# I2C.net
KiCad netlist of a schematic drawn in Altium Designer
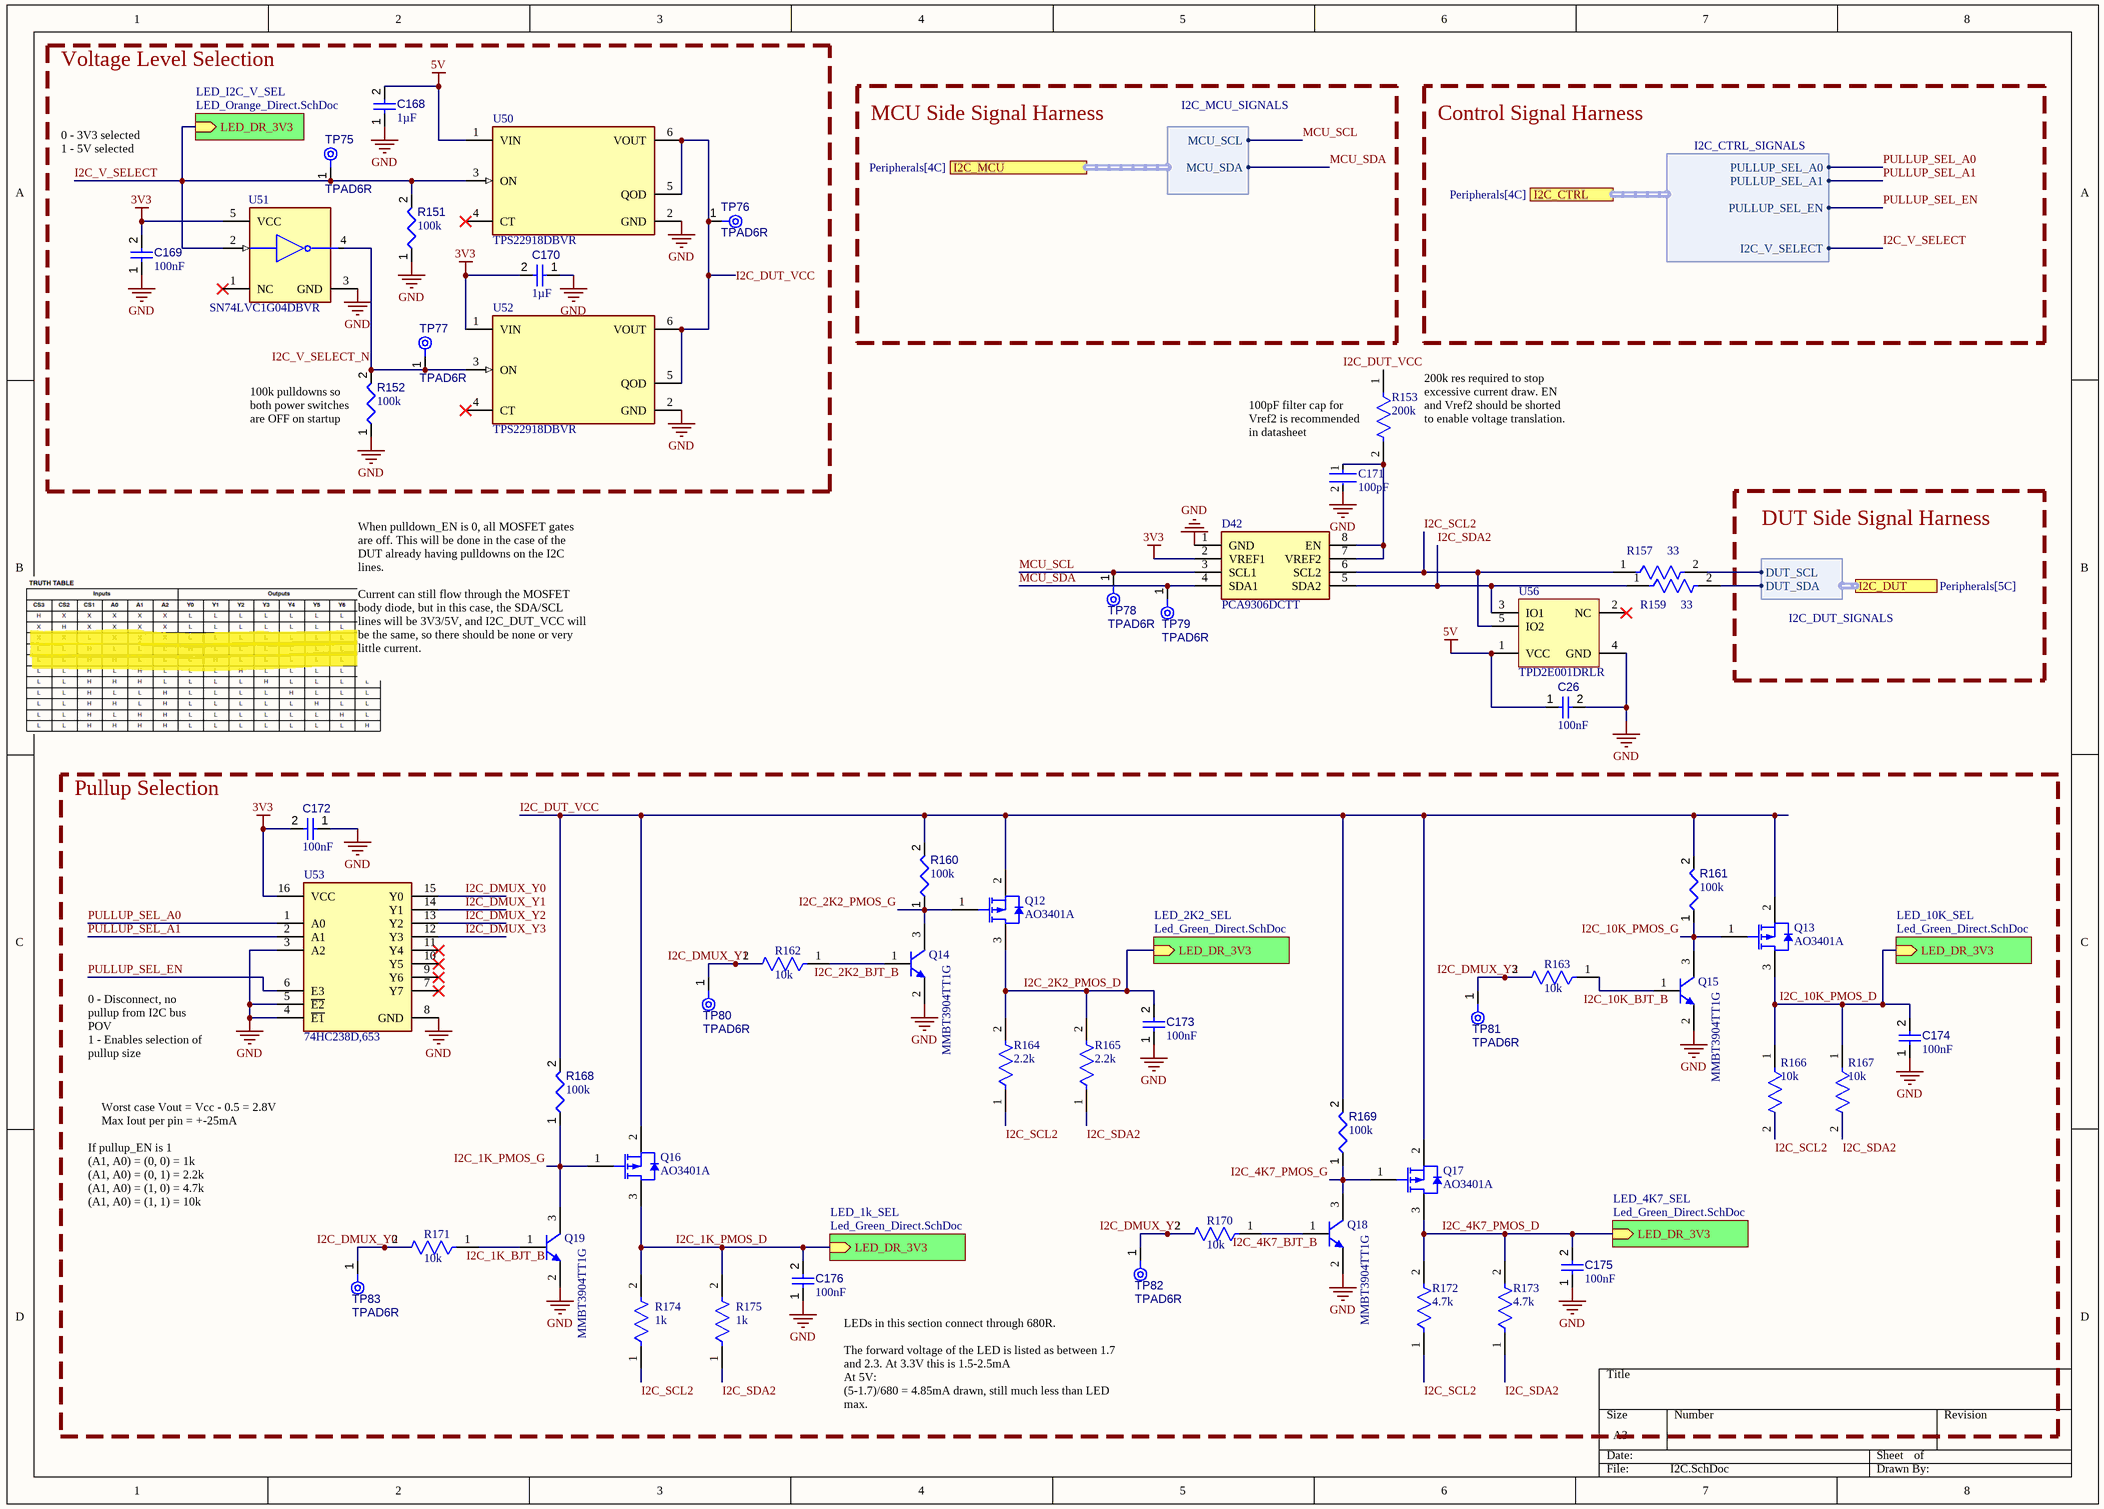
[diagram p0:  I2C.SchDoc]

(export (version "E")
  (design (tool "Eeschema 10.0.6"))
  (components
    (comp (ref "C26")
      (value "100nF")
      (footprint "CAPC1608X90X40NL10T20")
      (description "Chip Capacitor, 100 nF, +/- 10%, 50 V, 0603 (1608 Metric)")
      (fields (field (name "TOLERANCE") "10%") (field (name "Comment") "Capacitor 100 nF +/-10% 50 V 0603"))
      (libsource (lib "HIL RIG FYP") (part "CAP-NP-2"))
    )
    (comp (ref "C168")
      (value "1µF")
      (footprint "CAPC1608X90X40LL10T20")
      (description "Chip Capacitor, 1 uF, +/- 10%, 25 V, 0603 (1608 Metric)")
      (fields (field (name "TOLERANCE") "10%") (field (name "Comment") "Capacitor 1 uF +/- 10% 25 V 0603"))
      (libsource (lib "HIL RIG FYP") (part "CAP-NP-2"))
    )
    (comp (ref "C169")
      (value "100nF")
      (footprint "CAPC1608X90X40NL10T20")
      (description "Chip Capacitor, 100 nF, +/- 10%, 50 V, 0603 (1608 Metric)")
      (fields (field (name "TOLERANCE") "10%") (field (name "Comment") "Capacitor 100 nF +/-10% 50 V 0603"))
      (libsource (lib "HIL RIG FYP") (part "CAP-NP-2"))
    )
    (comp (ref "C170")
      (value "1µF")
      (footprint "CAPC1608X90X40LL10T20")
      (description "Chip Capacitor, 1 uF, +/- 10%, 25 V, 0603 (1608 Metric)")
      (fields (field (name "TOLERANCE") "10%") (field (name "Comment") "Capacitor 1 uF +/- 10% 25 V 0603"))
      (libsource (lib "HIL RIG FYP") (part "CAP-NP-2"))
    )
    (comp (ref "C171")
      (value "100pF")
      (footprint "FP-C0603C-CF-IPC_B")
      (description "50V 100pF C0G ±1% 0603 Multilayer Ceramic Capacitors MLCC - SMD/SMT ROHS")
      (fields (field (name "TOLERANCE") "1%") (field (name "Comment") "C0603C101F5GACTU"))
      (libsource (lib "HIL RIG FYP") (part "b4654b650e69147ec39a6b967a45e02"))
    )
    (comp (ref "C172")
      (value "100nF")
      (footprint "CAPC1608X90X40NL10T20")
      (description "Chip Capacitor, 100 nF, +/- 10%, 50 V, 0603 (1608 Metric)")
      (fields (field (name "TOLERANCE") "10%") (field (name "Comment") "Capacitor 100 nF +/-10% 50 V 0603"))
      (libsource (lib "HIL RIG FYP") (part "CAP-NP-2"))
    )
    (comp (ref "C173")
      (value "100nF")
      (footprint "CAPC1608X90X40NL10T20")
      (description "Chip Capacitor, 100 nF, +/- 10%, 50 V, 0603 (1608 Metric)")
      (fields (field (name "TOLERANCE") "10%") (field (name "Comment") "Capacitor 100 nF +/-10% 50 V 0603"))
      (libsource (lib "HIL RIG FYP") (part "CAP-NP-2"))
    )
    (comp (ref "C174")
      (value "100nF")
      (footprint "CAPC1608X90X40NL10T20")
      (description "Chip Capacitor, 100 nF, +/- 10%, 50 V, 0603 (1608 Metric)")
      (fields (field (name "TOLERANCE") "10%") (field (name "Comment") "Capacitor 100 nF +/-10% 50 V 0603"))
      (libsource (lib "HIL RIG FYP") (part "CAP-NP-2"))
    )
    (comp (ref "C175")
      (value "100nF")
      (footprint "CAPC1608X90X40NL10T20")
      (description "Chip Capacitor, 100 nF, +/- 10%, 50 V, 0603 (1608 Metric)")
      (fields (field (name "TOLERANCE") "10%") (field (name "Comment") "Capacitor 100 nF +/-10% 50 V 0603"))
      (libsource (lib "HIL RIG FYP") (part "CAP-NP-2"))
    )
    (comp (ref "C176")
      (value "100nF")
      (footprint "CAPC1608X90X40NL10T20")
      (description "Chip Capacitor, 100 nF, +/- 10%, 50 V, 0603 (1608 Metric)")
      (fields (field (name "TOLERANCE") "10%") (field (name "Comment") "Capacitor 100 nF +/-10% 50 V 0603"))
      (libsource (lib "HIL RIG FYP") (part "CAP-NP-2"))
    )
    (comp (ref "D42")
      (value "PCA9306DCTT")
      (footprint "SOP65P400X130-8N")
      (description "2-Bit Bidirectional I2C Bus and SMBus Voltage-Level Shifter")
      (fields (field (name "MOUSER PART NUMBER") "595-PCA9306DCTT"))
      (libsource (lib "HIL RIG FYP") (part "PCA9306DCTT"))
    )
    (comp (ref "Q12")
      (value "AO3401A")
      (footprint "AO-SOT-23-3L_V")
      (description "Transistor: P-MOSFET; unipolar; -30V; 4, 2A; 1, 4W; 85 mOhm; ; -55+150 st.C; SMD; SOT23")
      (libsource (lib "HIL RIG FYP") (part "PEMOS-GSD-3"))
    )
    (comp (ref "Q13")
      (value "AO3401A")
      (footprint "AO-SOT-23-3L_V")
      (description "Transistor: P-MOSFET; unipolar; -30V; 4, 2A; 1, 4W; 85 mOhm; ; -55+150 st.C; SMD; SOT23")
      (libsource (lib "HIL RIG FYP") (part "PEMOS-GSD-3"))
    )
    (comp (ref "Q14")
      (value "MMBT3904TT1G")
      (footprint "ONSC-SC-75-3-463-01_V")
      (description "on Semi MMBT3904TT1G NPN Bipolar Transistor, 0.2 A, 40 V, 3-PIN SOT-416")
      (libsource (lib "HIL RIG FYP") (part "ONSC-NPN-B1E2C3-3"))
    )
    (comp (ref "Q15")
      (value "MMBT3904TT1G")
      (footprint "ONSC-SC-75-3-463-01_V")
      (description "on Semi MMBT3904TT1G NPN Bipolar Transistor, 0.2 A, 40 V, 3-PIN SOT-416")
      (libsource (lib "HIL RIG FYP") (part "ONSC-NPN-B1E2C3-3"))
    )
    (comp (ref "Q16")
      (value "AO3401A")
      (footprint "AO-SOT-23-3L_V")
      (description "Transistor: P-MOSFET; unipolar; -30V; 4, 2A; 1, 4W; 85 mOhm; ; -55+150 st.C; SMD; SOT23")
      (libsource (lib "HIL RIG FYP") (part "PEMOS-GSD-3"))
    )
    (comp (ref "Q17")
      (value "AO3401A")
      (footprint "AO-SOT-23-3L_V")
      (description "Transistor: P-MOSFET; unipolar; -30V; 4, 2A; 1, 4W; 85 mOhm; ; -55+150 st.C; SMD; SOT23")
      (libsource (lib "HIL RIG FYP") (part "PEMOS-GSD-3"))
    )
    (comp (ref "Q18")
      (value "MMBT3904TT1G")
      (footprint "ONSC-SC-75-3-463-01_V")
      (description "on Semi MMBT3904TT1G NPN Bipolar Transistor, 0.2 A, 40 V, 3-PIN SOT-416")
      (libsource (lib "HIL RIG FYP") (part "ONSC-NPN-B1E2C3-3"))
    )
    (comp (ref "Q19")
      (value "MMBT3904TT1G")
      (footprint "ONSC-SC-75-3-463-01_V")
      (description "on Semi MMBT3904TT1G NPN Bipolar Transistor, 0.2 A, 40 V, 3-PIN SOT-416")
      (libsource (lib "HIL RIG FYP") (part "ONSC-NPN-B1E2C3-3"))
    )
    (comp (ref "R151")
      (value "100k")
      (footprint "FP-AC0603-IPC_C")
      (description "Res Thick Film 0603 100K Ohm 1% 0.1W(1/10W) ±100ppm/C Pad SMD T/R Automotive")
      (fields (field (name "TOLERANCE") "1%") (field (name "Comment") "AC0603FR-07100KL"))
      (libsource (lib "HIL RIG FYP") (part "RES-2"))
    )
    (comp (ref "R152")
      (value "100k")
      (footprint "FP-AC0603-IPC_C")
      (description "Res Thick Film 0603 100K Ohm 1% 0.1W(1/10W) ±100ppm/C Pad SMD T/R Automotive")
      (fields (field (name "TOLERANCE") "1%") (field (name "Comment") "AC0603FR-07100KL"))
      (libsource (lib "HIL RIG FYP") (part "RES-2"))
    )
    (comp (ref "R153")
      (value "200k")
      (footprint "FP-AT0603-IPC_A")
      (description "100mW Thin Film Resistor ±25ppm/℃ ±0.1% 200kΩ 0603 Chip Resistor - Surface Mount ROHS")
      (fields (field (name "TOLERANCE") "0.1%") (field (name "Comment") "AT0603BRD07200KL"))
      (libsource (lib "HIL RIG FYP") (part "1029c3af85768c4190bb7ad29bc67b5"))
    )
    (comp (ref "R157")
      (value "33")
      (footprint "FP-AC0603-IPC_C")
      (description "Res Thick Film 0603 33 Ohm 1% 0.1W(1/10W) ±100ppm/C Pad SMD T/R Automotive AEC-Q200")
      (fields (field (name "TOLERANCE") "1%") (field (name "Comment") "AC0603FR-0733RL"))
      (libsource (lib "HIL RIG FYP") (part "1029c3af85768c4190bb7ad29bc67b5"))
    )
    (comp (ref "R159")
      (value "33")
      (footprint "FP-AC0603-IPC_C")
      (description "Res Thick Film 0603 33 Ohm 1% 0.1W(1/10W) ±100ppm/C Pad SMD T/R Automotive AEC-Q200")
      (fields (field (name "TOLERANCE") "1%") (field (name "Comment") "AC0603FR-0733RL"))
      (libsource (lib "HIL RIG FYP") (part "1029c3af85768c4190bb7ad29bc67b5"))
    )
    (comp (ref "R160")
      (value "100k")
      (footprint "FP-AC0603-IPC_C")
      (description "Res Thick Film 0603 100K Ohm 1% 0.1W(1/10W) ±100ppm/C Pad SMD T/R Automotive")
      (fields (field (name "TOLERANCE") "1%") (field (name "Comment") "AC0603FR-07100KL"))
      (libsource (lib "HIL RIG FYP") (part "RES-2"))
    )
    (comp (ref "R161")
      (value "100k")
      (footprint "FP-AC0603-IPC_C")
      (description "Res Thick Film 0603 100K Ohm 1% 0.1W(1/10W) ±100ppm/C Pad SMD T/R Automotive")
      (fields (field (name "TOLERANCE") "1%") (field (name "Comment") "AC0603FR-07100KL"))
      (libsource (lib "HIL RIG FYP") (part "RES-2"))
    )
    (comp (ref "R162")
      (value "10k")
      (footprint "FP-RT0603-IPC_C")
      (description "Res Thin Film 0603 10K Ohm 0.1% 1/10W ¦25ppm/¦C SMD Paper T/R")
      (fields (field (name "TOLERANCE") "0.1%") (field (name "Comment") "RT0603BRD0710KL"))
      (libsource (lib "HIL RIG FYP") (part "1029c3af85768c4190bb7ad29bc67b5"))
    )
    (comp (ref "R163")
      (value "10k")
      (footprint "FP-RT0603-IPC_C")
      (description "Res Thin Film 0603 10K Ohm 0.1% 1/10W ¦25ppm/¦C SMD Paper T/R")
      (fields (field (name "TOLERANCE") "0.1%") (field (name "Comment") "RT0603BRD0710KL"))
      (libsource (lib "HIL RIG FYP") (part "1029c3af85768c4190bb7ad29bc67b5"))
    )
    (comp (ref "R164")
      (value "2.2k")
      (footprint "FP-RT0603-IPC_C")
      (description "100mW Thin Film Resistor 75V ±25ppm/℃ ±0.1% 2.2kΩ 0603 Chip Resistor - Surface Mount ROHS")
      (fields (field (name "TOLERANCE") "0.1%") (field (name "Comment") "RT0603BRD072K2L"))
      (libsource (lib "HIL RIG FYP") (part "1029c3af85768c4190bb7ad29bc67b5"))
    )
    (comp (ref "R165")
      (value "2.2k")
      (footprint "FP-RT0603-IPC_C")
      (description "100mW Thin Film Resistor 75V ±25ppm/℃ ±0.1% 2.2kΩ 0603 Chip Resistor - Surface Mount ROHS")
      (fields (field (name "TOLERANCE") "0.1%") (field (name "Comment") "RT0603BRD072K2L"))
      (libsource (lib "HIL RIG FYP") (part "1029c3af85768c4190bb7ad29bc67b5"))
    )
    (comp (ref "R166")
      (value "10k")
      (footprint "FP-RT0603-IPC_C")
      (description "Res Thin Film 0603 10K Ohm 0.1% 1/10W ¦25ppm/¦C SMD Paper T/R")
      (fields (field (name "TOLERANCE") "0.1%") (field (name "Comment") "RT0603BRD0710KL"))
      (libsource (lib "HIL RIG FYP") (part "1029c3af85768c4190bb7ad29bc67b5"))
    )
    (comp (ref "R167")
      (value "10k")
      (footprint "FP-RT0603-IPC_C")
      (description "Res Thin Film 0603 10K Ohm 0.1% 1/10W ¦25ppm/¦C SMD Paper T/R")
      (fields (field (name "TOLERANCE") "0.1%") (field (name "Comment") "RT0603BRD0710KL"))
      (libsource (lib "HIL RIG FYP") (part "1029c3af85768c4190bb7ad29bc67b5"))
    )
    (comp (ref "R168")
      (value "100k")
      (footprint "FP-AC0603-IPC_C")
      (description "Res Thick Film 0603 100K Ohm 1% 0.1W(1/10W) ±100ppm/C Pad SMD T/R Automotive")
      (fields (field (name "TOLERANCE") "1%") (field (name "Comment") "AC0603FR-07100KL"))
      (libsource (lib "HIL RIG FYP") (part "RES-2"))
    )
    (comp (ref "R169")
      (value "100k")
      (footprint "FP-AC0603-IPC_C")
      (description "Res Thick Film 0603 100K Ohm 1% 0.1W(1/10W) ±100ppm/C Pad SMD T/R Automotive")
      (fields (field (name "TOLERANCE") "1%") (field (name "Comment") "AC0603FR-07100KL"))
      (libsource (lib "HIL RIG FYP") (part "RES-2"))
    )
    (comp (ref "R170")
      (value "10k")
      (footprint "FP-RT0603-IPC_C")
      (description "Res Thin Film 0603 10K Ohm 0.1% 1/10W ¦25ppm/¦C SMD Paper T/R")
      (fields (field (name "TOLERANCE") "0.1%") (field (name "Comment") "RT0603BRD0710KL"))
      (libsource (lib "HIL RIG FYP") (part "1029c3af85768c4190bb7ad29bc67b5"))
    )
    (comp (ref "R171")
      (value "10k")
      (footprint "FP-RT0603-IPC_C")
      (description "Res Thin Film 0603 10K Ohm 0.1% 1/10W ¦25ppm/¦C SMD Paper T/R")
      (fields (field (name "TOLERANCE") "0.1%") (field (name "Comment") "RT0603BRD0710KL"))
      (libsource (lib "HIL RIG FYP") (part "1029c3af85768c4190bb7ad29bc67b5"))
    )
    (comp (ref "R172")
      (value "4.7k")
      (footprint "FP-RT0603-IPC_C")
      (description "Res Thin Film 0603 4.7K Ohm 0.1% 0.1W(1/10W) ±25ppm/C Pad SMD T/R")
      (fields (field (name "TOLERANCE") "0.1%") (field (name "Comment") "RT0603BRD074K7L"))
      (libsource (lib "HIL RIG FYP") (part "1029c3af85768c4190bb7ad29bc67b5"))
    )
    (comp (ref "R173")
      (value "4.7k")
      (footprint "FP-RT0603-IPC_C")
      (description "Res Thin Film 0603 4.7K Ohm 0.1% 0.1W(1/10W) ±25ppm/C Pad SMD T/R")
      (fields (field (name "TOLERANCE") "0.1%") (field (name "Comment") "RT0603BRD074K7L"))
      (libsource (lib "HIL RIG FYP") (part "1029c3af85768c4190bb7ad29bc67b5"))
    )
    (comp (ref "R174")
      (value "1k")
      (footprint "FP-RT0603-IPC_B")
      (description "100mW Thin Film Resistor 75V ±25ppm/℃ ±0.1% 1kΩ 0603 Chip Resistor - Surface Mount ROHS")
      (fields (field (name "TOLERANCE") "0.1%") (field (name "Comment") "RT0603BRD071KL"))
      (libsource (lib "HIL RIG FYP") (part "1029c3af85768c4190bb7ad29bc67b5"))
    )
    (comp (ref "R175")
      (value "1k")
      (footprint "FP-RT0603-IPC_B")
      (description "100mW Thin Film Resistor 75V ±25ppm/℃ ±0.1% 1kΩ 0603 Chip Resistor - Surface Mount ROHS")
      (fields (field (name "TOLERANCE") "0.1%") (field (name "Comment") "RT0603BRD071KL"))
      (libsource (lib "HIL RIG FYP") (part "1029c3af85768c4190bb7ad29bc67b5"))
    )
    (comp (ref "TP75")
      (value "TPAD6R")
      (footprint "TP06R")
      (description "0.6mm round")
      (libsource (lib "HIL RIG FYP") (part "CMP-001-0001-4"))
    )
    (comp (ref "TP76")
      (value "TPAD6R")
      (footprint "TP06R")
      (description "0.6mm round")
      (libsource (lib "HIL RIG FYP") (part "CMP-001-0001-4"))
    )
    (comp (ref "TP77")
      (value "TPAD6R")
      (footprint "TP06R")
      (description "0.6mm round")
      (libsource (lib "HIL RIG FYP") (part "CMP-001-0001-4"))
    )
    (comp (ref "TP78")
      (value "TPAD6R")
      (footprint "TP06R")
      (description "0.6mm round")
      (libsource (lib "HIL RIG FYP") (part "CMP-001-0001-4"))
    )
    (comp (ref "TP79")
      (value "TPAD6R")
      (footprint "TP06R")
      (description "0.6mm round")
      (libsource (lib "HIL RIG FYP") (part "CMP-001-0001-4"))
    )
    (comp (ref "TP80")
      (value "TPAD6R")
      (footprint "TP06R")
      (description "0.6mm round")
      (libsource (lib "HIL RIG FYP") (part "CMP-001-0001-4"))
    )
    (comp (ref "TP81")
      (value "TPAD6R")
      (footprint "TP06R")
      (description "0.6mm round")
      (libsource (lib "HIL RIG FYP") (part "CMP-001-0001-4"))
    )
    (comp (ref "TP82")
      (value "TPAD6R")
      (footprint "TP06R")
      (description "0.6mm round")
      (libsource (lib "HIL RIG FYP") (part "CMP-001-0001-4"))
    )
    (comp (ref "TP83")
      (value "TPAD6R")
      (footprint "TP06R")
      (description "0.6mm round")
      (libsource (lib "HIL RIG FYP") (part "CMP-001-0001-4"))
    )
    (comp (ref "U50")
      (value "TPS22918DBVR")
      (footprint "FP-DBV0006A-IPC_B")
      (description "5.5-V, 2-A, 52-mΩ load switch with adj. rise time and adj. output discharge 6-SOT-23 -40 to 105")
      (libsource (lib "HIL RIG FYP") (part "9788e20321289e35c69900ab3a2f991"))
    )
    (comp (ref "U51")
      (value "SN74LVC1G04DBVR")
      (footprint "FP-DBV0005A-IPC_B")
      (description "SINGLE INVERTER GATE Inverter, LVC/LCX/Z Series, 1-Func, 1-Input, CMOS, PDSO5")
      (libsource (lib "HIL RIG FYP") (part "d8ebd454d5f67517583d36c9dc32b5e"))
    )
    (comp (ref "U52")
      (value "TPS22918DBVR")
      (footprint "FP-DBV0006A-IPC_B")
      (description "5.5-V, 2-A, 52-mΩ load switch with adj. rise time and adj. output discharge 6-SOT-23 -40 to 105")
      (libsource (lib "HIL RIG FYP") (part "9788e20321289e35c69900ab3a2f991"))
    )
    (comp (ref "U53")
      (value "74HC238D,653")
      (footprint "74HC238D653")
      (description "74HC(T)238 - 3-to-8 line decoder/demultiplexer@en-us")
      (fields (field (name "MOUSER PART NUMBER") "771-74HC238D-T"))
      (libsource (lib "HIL RIG FYP") (part "74HC238D,653"))
    )
    (comp (ref "U56")
      (value "TPD2E001DRLR")
      (footprint "DRL0005A_M")
      (description "11V Unidirectional 5.5V SOT-553-5 ESD and Surge Protection (TVS/ESD) ROHS")
      (libsource (lib "HIL RIG FYP") (part "TI-TPD2E001-SOT_DRL-5"))
    )
  )
  (nets
    (net (code "4") (name "/DUT_SCL") (class "Default")
      (node (ref "R157") (pin "2") (pinfunction "2_2") (pintype "passive"))
    )
    (net (code "5") (name "/DUT_SDA") (class "Default")
      (node (ref "R159") (pin "2") (pinfunction "2_2") (pintype "passive"))
    )
    (net (code "6") (name "/I2C_1K_BJT_B") (class "Default")
      (node (ref "Q19") (pin "1") (pinfunction "B_1") (pintype "passive"))
      (node (ref "R171") (pin "1") (pinfunction "1_1") (pintype "passive"))
    )
    (net (code "7") (name "/I2C_1K_PMOS_D") (class "Default")
      (node (ref "C176") (pin "2") (pinfunction "2_2") (pintype "passive"))
      (node (ref "Q16") (pin "3") (pinfunction "DRAIN_3") (pintype "passive"))
      (node (ref "R174") (pin "2") (pinfunction "2_2") (pintype "passive"))
      (node (ref "R175") (pin "2") (pinfunction "2_2") (pintype "passive"))
    )
    (net (code "8") (name "/I2C_1K_PMOS_G") (class "Default")
      (node (ref "Q16") (pin "1") (pinfunction "GATE_1") (pintype "passive"))
      (node (ref "Q19") (pin "3") (pinfunction "C_3") (pintype "passive"))
      (node (ref "R168") (pin "1") (pinfunction "1_1") (pintype "passive"))
    )
    (net (code "9") (name "/I2C_2K2_BJT_B") (class "Default")
      (node (ref "Q14") (pin "1") (pinfunction "B_1") (pintype "passive"))
      (node (ref "R162") (pin "1") (pinfunction "1_1") (pintype "passive"))
    )
    (net (code "10") (name "/I2C_2K2_PMOS_D") (class "Default")
      (node (ref "C173") (pin "2") (pinfunction "2_2") (pintype "passive"))
      (node (ref "Q12") (pin "3") (pinfunction "DRAIN_3") (pintype "passive"))
      (node (ref "R164") (pin "2") (pinfunction "2_2") (pintype "passive"))
      (node (ref "R165") (pin "2") (pinfunction "2_2") (pintype "passive"))
    )
    (net (code "11") (name "/I2C_2K2_PMOS_G") (class "Default")
      (node (ref "Q12") (pin "1") (pinfunction "GATE_1") (pintype "passive"))
      (node (ref "Q14") (pin "3") (pinfunction "C_3") (pintype "passive"))
      (node (ref "R160") (pin "1") (pinfunction "1_1") (pintype "passive"))
    )
    (net (code "12") (name "/I2C_4K7_BJT_B") (class "Default")
      (node (ref "Q18") (pin "1") (pinfunction "B_1") (pintype "passive"))
      (node (ref "R170") (pin "1") (pinfunction "1_1") (pintype "passive"))
    )
    (net (code "13") (name "/I2C_4K7_PMOS_D") (class "Default")
      (node (ref "C175") (pin "2") (pinfunction "2_2") (pintype "passive"))
      (node (ref "Q17") (pin "3") (pinfunction "DRAIN_3") (pintype "passive"))
      (node (ref "R172") (pin "2") (pinfunction "2_2") (pintype "passive"))
      (node (ref "R173") (pin "2") (pinfunction "2_2") (pintype "passive"))
    )
    (net (code "14") (name "/I2C_4K7_PMOS_G") (class "Default")
      (node (ref "Q17") (pin "1") (pinfunction "GATE_1") (pintype "passive"))
      (node (ref "Q18") (pin "3") (pinfunction "C_3") (pintype "passive"))
      (node (ref "R169") (pin "1") (pinfunction "1_1") (pintype "passive"))
    )
    (net (code "15") (name "/I2C_10K_BJT_B") (class "Default")
      (node (ref "Q15") (pin "1") (pinfunction "B_1") (pintype "passive"))
      (node (ref "R163") (pin "1") (pinfunction "1_1") (pintype "passive"))
    )
    (net (code "16") (name "/I2C_10K_PMOS_D") (class "Default")
      (node (ref "C174") (pin "2") (pinfunction "2_2") (pintype "passive"))
      (node (ref "Q13") (pin "3") (pinfunction "DRAIN_3") (pintype "passive"))
      (node (ref "R166") (pin "1") (pinfunction "1_1") (pintype "passive"))
      (node (ref "R167") (pin "1") (pinfunction "1_1") (pintype "passive"))
    )
    (net (code "17") (name "/I2C_10K_PMOS_G") (class "Default")
      (node (ref "Q13") (pin "1") (pinfunction "GATE_1") (pintype "passive"))
      (node (ref "Q15") (pin "3") (pinfunction "C_3") (pintype "passive"))
      (node (ref "R161") (pin "1") (pinfunction "1_1") (pintype "passive"))
    )
    (net (code "18") (name "/I2C_DMUX_Y0") (class "Default")
      (node (ref "R171") (pin "2") (pinfunction "2_2") (pintype "passive"))
      (node (ref "TP83") (pin "1") (pinfunction "TP_1") (pintype "passive"))
      (node (ref "U53") (pin "15") (pinfunction "Y0_15") (pintype "passive"))
    )
    (net (code "19") (name "/I2C_DMUX_Y1") (class "Default")
      (node (ref "R162") (pin "2") (pinfunction "2_2") (pintype "passive"))
      (node (ref "TP80") (pin "1") (pinfunction "TP_1") (pintype "passive"))
      (node (ref "U53") (pin "14") (pinfunction "Y1_14") (pintype "passive"))
    )
    (net (code "20") (name "/I2C_DMUX_Y2") (class "Default")
      (node (ref "R170") (pin "2") (pinfunction "2_2") (pintype "passive"))
      (node (ref "TP82") (pin "1") (pinfunction "TP_1") (pintype "passive"))
      (node (ref "U53") (pin "13") (pinfunction "Y2_13") (pintype "passive"))
    )
    (net (code "21") (name "/I2C_DMUX_Y3") (class "Default")
      (node (ref "R163") (pin "2") (pinfunction "2_2") (pintype "passive"))
      (node (ref "TP81") (pin "1") (pinfunction "TP_1") (pintype "passive"))
      (node (ref "U53") (pin "12") (pinfunction "Y3_12") (pintype "passive"))
    )
    (net (code "22") (name "/I2C_DUT_VCC") (class "Default")
      (node (ref "Q12") (pin "2") (pinfunction "SOURCE_2") (pintype "passive"))
      (node (ref "Q13") (pin "2") (pinfunction "SOURCE_2") (pintype "passive"))
      (node (ref "Q16") (pin "2") (pinfunction "SOURCE_2") (pintype "passive"))
      (node (ref "Q17") (pin "2") (pinfunction "SOURCE_2") (pintype "passive"))
      (node (ref "R153") (pin "1") (pinfunction "1_1") (pintype "passive"))
      (node (ref "R160") (pin "2") (pinfunction "2_2") (pintype "passive"))
      (node (ref "R161") (pin "2") (pinfunction "2_2") (pintype "passive"))
      (node (ref "R168") (pin "2") (pinfunction "2_2") (pintype "passive"))
      (node (ref "R169") (pin "2") (pinfunction "2_2") (pintype "passive"))
      (node (ref "TP76") (pin "1") (pinfunction "TP_1") (pintype "passive"))
      (node (ref "U50") (pin "5") (pinfunction "QOD_5") (pintype "passive"))
      (node (ref "U50") (pin "6") (pinfunction "VOUT_6") (pintype "passive"))
      (node (ref "U52") (pin "5") (pinfunction "QOD_5") (pintype "passive"))
      (node (ref "U52") (pin "6") (pinfunction "VOUT_6") (pintype "passive"))
    )
    (net (code "23") (name "/I2C_SCL2") (class "Default")
      (node (ref "D42") (pin "6") (pinfunction "SCL2_6") (pintype "passive"))
      (node (ref "R157") (pin "1") (pinfunction "1_1") (pintype "passive"))
      (node (ref "R164") (pin "1") (pinfunction "1_1") (pintype "passive"))
      (node (ref "R166") (pin "2") (pinfunction "2_2") (pintype "passive"))
      (node (ref "R172") (pin "1") (pinfunction "1_1") (pintype "passive"))
      (node (ref "R174") (pin "1") (pinfunction "1_1") (pintype "passive"))
      (node (ref "U56") (pin "5") (pinfunction "IO2_5") (pintype "passive"))
    )
    (net (code "24") (name "/I2C_SDA2") (class "Default")
      (node (ref "D42") (pin "5") (pinfunction "SDA2_5") (pintype "passive"))
      (node (ref "R159") (pin "1") (pinfunction "1_1") (pintype "passive"))
      (node (ref "R165") (pin "1") (pinfunction "1_1") (pintype "passive"))
      (node (ref "R167") (pin "2") (pinfunction "2_2") (pintype "passive"))
      (node (ref "R173") (pin "1") (pinfunction "1_1") (pintype "passive"))
      (node (ref "R175") (pin "1") (pinfunction "1_1") (pintype "passive"))
      (node (ref "U56") (pin "3") (pinfunction "IO1_3") (pintype "passive"))
    )
    (net (code "25") (name "/I2C_V_SELECT") (class "Default")
      (node (ref "R151") (pin "2") (pinfunction "2_2") (pintype "passive"))
      (node (ref "TP75") (pin "1") (pinfunction "TP_1") (pintype "passive"))
      (node (ref "U50") (pin "3") (pinfunction "ON_3") (pintype "input"))
      (node (ref "U51") (pin "2") (pinfunction "A_2") (pintype "input"))
    )
    (net (code "26") (name "/I2C_V_SELECT_N") (class "Default")
      (node (ref "R152") (pin "2") (pinfunction "2_2") (pintype "passive"))
      (node (ref "TP77") (pin "1") (pinfunction "TP_1") (pintype "passive"))
      (node (ref "U51") (pin "4") (pinfunction "Y_4") (pintype "output"))
      (node (ref "U52") (pin "3") (pinfunction "ON_3") (pintype "input"))
    )
    (net (code "27") (name "/MCU_SCL") (class "Default")
      (node (ref "D42") (pin "3") (pinfunction "SCL1_3") (pintype "passive"))
      (node (ref "TP78") (pin "1") (pinfunction "TP_1") (pintype "passive"))
    )
    (net (code "28") (name "/MCU_SDA") (class "Default")
      (node (ref "D42") (pin "4") (pinfunction "SDA1_4") (pintype "passive"))
      (node (ref "TP79") (pin "1") (pinfunction "TP_1") (pintype "passive"))
    )
    (net (code "29") (name "/PULLUP_SEL_A0") (class "Default")
      (node (ref "U53") (pin "1") (pinfunction "A0_1") (pintype "passive"))
    )
    (net (code "30") (name "/PULLUP_SEL_A1") (class "Default")
      (node (ref "U53") (pin "2") (pinfunction "A1_2") (pintype "passive"))
    )
    (net (code "31") (name "/PULLUP_SEL_EN") (class "Default")
      (node (ref "U53") (pin "6") (pinfunction "E3_6") (pintype "passive"))
    )
    (net (code "35") (name "3V3") (class "Default")
      (node (ref "C169") (pin "2") (pinfunction "2_2") (pintype "passive"))
      (node (ref "C170") (pin "2") (pinfunction "2_2") (pintype "passive"))
      (node (ref "C172") (pin "2") (pinfunction "2_2") (pintype "passive"))
      (node (ref "D42") (pin "2") (pinfunction "VREF1_2") (pintype "passive"))
      (node (ref "U51") (pin "5") (pinfunction "VCC_5") (pintype "power_in"))
      (node (ref "U52") (pin "1") (pinfunction "VIN_1") (pintype "power_in"))
      (node (ref "U53") (pin "16") (pinfunction "VCC_16") (pintype "passive"))
    )
    (net (code "36") (name "5V") (class "Default")
      (node (ref "C168") (pin "2") (pinfunction "2_2") (pintype "passive"))
      (node (ref "C26") (pin "1") (pinfunction "1_1") (pintype "passive"))
      (node (ref "U50") (pin "1") (pinfunction "VIN_1") (pintype "power_in"))
      (node (ref "U56") (pin "1") (pinfunction "VCC_1") (pintype "power_in"))
    )
    (net (code "37") (name "GND") (class "Default")
      (node (ref "C168") (pin "1") (pinfunction "1_1") (pintype "passive"))
      (node (ref "C169") (pin "1") (pinfunction "1_1") (pintype "passive"))
      (node (ref "C170") (pin "1") (pinfunction "1_1") (pintype "passive"))
      (node (ref "C171") (pin "2") (pinfunction "2_2") (pintype "passive"))
      (node (ref "C172") (pin "1") (pinfunction "1_1") (pintype "passive"))
      (node (ref "C173") (pin "1") (pinfunction "1_1") (pintype "passive"))
      (node (ref "C174") (pin "1") (pinfunction "1_1") (pintype "passive"))
      (node (ref "C175") (pin "1") (pinfunction "1_1") (pintype "passive"))
      (node (ref "C176") (pin "1") (pinfunction "1_1") (pintype "passive"))
      (node (ref "C26") (pin "2") (pinfunction "2_2") (pintype "passive"))
      (node (ref "D42") (pin "1") (pinfunction "GND_1") (pintype "passive"))
      (node (ref "Q14") (pin "2") (pinfunction "E_2") (pintype "passive"))
      (node (ref "Q15") (pin "2") (pinfunction "E_2") (pintype "passive"))
      (node (ref "Q18") (pin "2") (pinfunction "E_2") (pintype "passive"))
      (node (ref "Q19") (pin "2") (pinfunction "E_2") (pintype "passive"))
      (node (ref "R151") (pin "1") (pinfunction "1_1") (pintype "passive"))
      (node (ref "R152") (pin "1") (pinfunction "1_1") (pintype "passive"))
      (node (ref "U50") (pin "2") (pinfunction "GND_2") (pintype "power_in"))
      (node (ref "U51") (pin "3") (pinfunction "GND_3") (pintype "power_in"))
      (node (ref "U52") (pin "2") (pinfunction "GND_2") (pintype "power_in"))
      (node (ref "U53") (pin "3") (pinfunction "A2_3") (pintype "passive"))
      (node (ref "U53") (pin "4") (pinfunction "~{E1}_4") (pintype "passive"))
      (node (ref "U53") (pin "5") (pinfunction "~{E2}_5") (pintype "passive"))
      (node (ref "U53") (pin "8") (pinfunction "GND_8") (pintype "passive"))
      (node (ref "U56") (pin "4") (pinfunction "GND_4") (pintype "power_in"))
    )
    (net (code "38") (name "Net-(D42-EN)") (class "Default")
      (node (ref "C171") (pin "1") (pinfunction "1_1") (pintype "passive"))
      (node (ref "D42") (pin "7") (pinfunction "VREF2_7") (pintype "passive"))
      (node (ref "D42") (pin "8") (pinfunction "EN_8") (pintype "passive"))
      (node (ref "R153") (pin "2") (pinfunction "2_2") (pintype "passive"))
    )
    (net (code "39") (name "unconnected-(U50-CT-Pad4)") (class "Default")
      (node (ref "U50") (pin "4") (pinfunction "CT_4") (pintype "passive+no_connect"))
    )
    (net (code "40") (name "unconnected-(U51-NC-Pad1)") (class "Default")
      (node (ref "U51") (pin "1") (pinfunction "NC_1") (pintype "passive+no_connect"))
    )
    (net (code "41") (name "unconnected-(U52-CT-Pad4)") (class "Default")
      (node (ref "U52") (pin "4") (pinfunction "CT_4") (pintype "passive+no_connect"))
    )
    (net (code "42") (name "unconnected-(U53-Y4-Pad11)") (class "Default")
      (node (ref "U53") (pin "11") (pinfunction "Y4_11") (pintype "passive+no_connect"))
    )
    (net (code "43") (name "unconnected-(U53-Y5-Pad10)") (class "Default")
      (node (ref "U53") (pin "10") (pinfunction "Y5_10") (pintype "passive+no_connect"))
    )
    (net (code "44") (name "unconnected-(U53-Y6-Pad9)") (class "Default")
      (node (ref "U53") (pin "9") (pinfunction "Y6_9") (pintype "passive+no_connect"))
    )
    (net (code "45") (name "unconnected-(U53-Y7-Pad7)") (class "Default")
      (node (ref "U53") (pin "7") (pinfunction "Y7_7") (pintype "passive+no_connect"))
    )
    (net (code "46") (name "unconnected-(U56-NC-Pad2)") (class "Default")
      (node (ref "U56") (pin "2") (pinfunction "NC_2") (pintype "passive+no_connect"))
    )
  )
)
